# deska.net
KiCad netlist of a schematic drawn in EAGLE
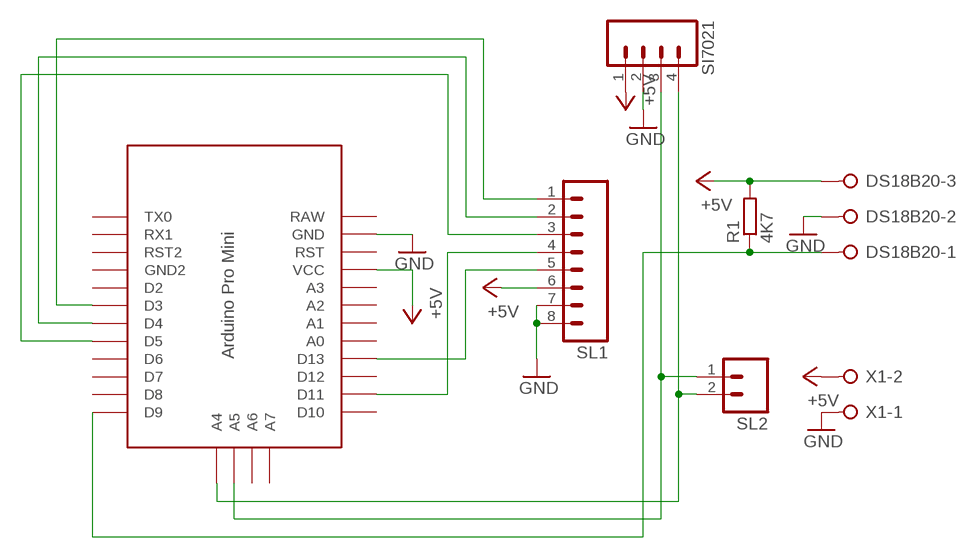
[diagram p0: schematic, sheet 1]

(export (version "E")
  (design (tool "Eeschema 10.0.6"))
  (components
    (comp (ref "DS18B20")
      (value "W237-03P")
      (footprint "eagle-import:W237-133")
      (libsource (lib "eagle-import") (part "W237-03P"))
    )
    (comp (ref "R1")
      (value "4K7")
      (footprint "eagle-import:0207_10")
      (libsource (lib "eagle-import") (part "R-EU_0207/10"))
    )
    (comp (ref "SI7021")
      (value "M04")
      (footprint "eagle-import:04P")
      (libsource (lib "eagle-import") (part "M04"))
    )
    (comp (ref "SL1")
      (value "M08")
      (footprint "eagle-import:08P")
      (libsource (lib "eagle-import") (part "M08"))
    )
    (comp (ref "SL2")
      (value "M02")
      (footprint "eagle-import:02P")
      (libsource (lib "eagle-import") (part "M02"))
    )
    (comp (ref "U$1")
      (value "PRO-MINI")
      (footprint "eagle-import:PRO-MINI")
      (libsource (lib "eagle-import") (part "PRO-MINI"))
    )
    (comp (ref "X1")
      (value "W237-02P")
      (footprint "eagle-import:W237-132")
      (libsource (lib "eagle-import") (part "W237-02P"))
    )
  )
  (nets
    (net (code "1") (name "+5V") (class "Default")
      (node (ref "DS18B20") (pin "3") (pinfunction "KL_3") (pintype "passive"))
      (node (ref "R1") (pin "2") (pinfunction "2_2") (pintype "passive"))
      (node (ref "SI7021") (pin "1") (pinfunction "1_1") (pintype "passive"))
      (node (ref "SL1") (pin "6") (pinfunction "6_6") (pintype "passive"))
      (node (ref "U$1") (pin "VCC") (pinfunction "VCC_VCC") (pintype "bidirectional"))
      (node (ref "X1") (pin "2") (pinfunction "KL_2") (pintype "passive"))
    )
    (net (code "2") (name "/RAW") (class "Default")
      (node (ref "U$1") (pin "RAW") (pinfunction "RAW_RAW") (pintype "power_in"))
    )
    (net (code "3") (name "GND") (class "Default")
      (node (ref "DS18B20") (pin "2") (pinfunction "KL_2") (pintype "passive"))
      (node (ref "SI7021") (pin "2") (pinfunction "2_2") (pintype "passive"))
      (node (ref "SL1") (pin "7") (pinfunction "7_7") (pintype "passive"))
      (node (ref "SL1") (pin "8") (pinfunction "8_8") (pintype "passive"))
      (node (ref "U$1") (pin "GND") (pinfunction "GND_GND") (pintype "input"))
      (node (ref "X1") (pin "1") (pinfunction "KL_1") (pintype "passive"))
    )
    (net (code "4") (name "Net-(DS18B20A-KL)") (class "Default")
      (node (ref "DS18B20") (pin "1") (pinfunction "KL_1") (pintype "passive"))
      (node (ref "R1") (pin "1") (pinfunction "1_1") (pintype "passive"))
      (node (ref "U$1") (pin "D9") (pinfunction "D9_D9") (pintype "bidirectional"))
    )
    (net (code "5") (name "Net-(SI7021-Pad3)") (class "Default")
      (node (ref "SI7021") (pin "3") (pinfunction "3_3") (pintype "passive"))
      (node (ref "SL2") (pin "1") (pinfunction "1_1") (pintype "passive"))
      (node (ref "U$1") (pin "A5") (pinfunction "A5_A5") (pintype "bidirectional"))
    )
    (net (code "6") (name "Net-(SI7021-Pad4)") (class "Default")
      (node (ref "SI7021") (pin "4") (pinfunction "4_4") (pintype "passive"))
      (node (ref "SL2") (pin "2") (pinfunction "2_2") (pintype "passive"))
      (node (ref "U$1") (pin "A4") (pinfunction "A4_A4") (pintype "bidirectional"))
    )
    (net (code "7") (name "Net-(SL1-Pad1)") (class "Default")
      (node (ref "SL1") (pin "1") (pinfunction "1_1") (pintype "passive"))
      (node (ref "U$1") (pin "D3") (pinfunction "D3_D3") (pintype "bidirectional"))
    )
    (net (code "8") (name "Net-(SL1-Pad2)") (class "Default")
      (node (ref "SL1") (pin "2") (pinfunction "2_2") (pintype "passive"))
      (node (ref "U$1") (pin "D4") (pinfunction "D4_D4") (pintype "bidirectional"))
    )
    (net (code "9") (name "Net-(SL1-Pad3)") (class "Default")
      (node (ref "SL1") (pin "3") (pinfunction "3_3") (pintype "passive"))
      (node (ref "U$1") (pin "D5") (pinfunction "D5_D5") (pintype "bidirectional"))
    )
    (net (code "10") (name "Net-(SL1-Pad4)") (class "Default")
      (node (ref "SL1") (pin "4") (pinfunction "4_4") (pintype "passive"))
      (node (ref "U$1") (pin "D11") (pinfunction "D11_D11") (pintype "bidirectional"))
    )
    (net (code "11") (name "Net-(SL1-Pad5)") (class "Default")
      (node (ref "SL1") (pin "5") (pinfunction "5_5") (pintype "passive"))
      (node (ref "U$1") (pin "D13") (pinfunction "D13_D13") (pintype "bidirectional"))
    )
    (net (code "12") (name "unconnected-(U$1-GND2-PadGND1)") (class "Default")
      (node (ref "U$1") (pin "GND1") (pinfunction "GND2_GND1") (pintype "bidirectional"))
    )
    (net (code "13") (name "unconnected-(U$1-PadA0)") (class "Default")
      (node (ref "U$1") (pin "A0") (pinfunction "A0_A0") (pintype "bidirectional"))
    )
    (net (code "14") (name "unconnected-(U$1-PadA1)") (class "Default")
      (node (ref "U$1") (pin "A1") (pinfunction "A1_A1") (pintype "bidirectional"))
    )
    (net (code "15") (name "unconnected-(U$1-PadA2)") (class "Default")
      (node (ref "U$1") (pin "A2") (pinfunction "A2_A2") (pintype "bidirectional"))
    )
    (net (code "16") (name "unconnected-(U$1-PadA3)") (class "Default")
      (node (ref "U$1") (pin "A3") (pinfunction "A3_A3") (pintype "bidirectional"))
    )
    (net (code "17") (name "unconnected-(U$1-PadA6)") (class "Default")
      (node (ref "U$1") (pin "A6") (pinfunction "A6_A6") (pintype "bidirectional"))
    )
    (net (code "18") (name "unconnected-(U$1-PadA7)") (class "Default")
      (node (ref "U$1") (pin "A7") (pinfunction "A7_A7") (pintype "bidirectional"))
    )
    (net (code "19") (name "unconnected-(U$1-PadD2)") (class "Default")
      (node (ref "U$1") (pin "D2") (pinfunction "D2_D2") (pintype "bidirectional"))
    )
    (net (code "20") (name "unconnected-(U$1-PadD6)") (class "Default")
      (node (ref "U$1") (pin "D6") (pinfunction "D6_D6") (pintype "bidirectional"))
    )
    (net (code "21") (name "unconnected-(U$1-PadD7)") (class "Default")
      (node (ref "U$1") (pin "D7") (pinfunction "D7_D7") (pintype "bidirectional"))
    )
    (net (code "22") (name "unconnected-(U$1-PadD8)") (class "Default")
      (node (ref "U$1") (pin "D8") (pinfunction "D8_D8") (pintype "bidirectional"))
    )
    (net (code "23") (name "unconnected-(U$1-PadD10)") (class "Default")
      (node (ref "U$1") (pin "D10") (pinfunction "D10_D10") (pintype "bidirectional"))
    )
    (net (code "24") (name "unconnected-(U$1-PadD12)") (class "Default")
      (node (ref "U$1") (pin "D12") (pinfunction "D12_D12") (pintype "bidirectional"))
    )
    (net (code "25") (name "unconnected-(U$1-PadRST)") (class "Default")
      (node (ref "U$1") (pin "RST") (pinfunction "RST_RST") (pintype "bidirectional"))
    )
    (net (code "26") (name "unconnected-(U$1-PadRX1)") (class "Default")
      (node (ref "U$1") (pin "RX1") (pinfunction "RX1_RX1") (pintype "bidirectional"))
    )
    (net (code "27") (name "unconnected-(U$1-PadTX0)") (class "Default")
      (node (ref "U$1") (pin "TX0") (pinfunction "TX0_TX0") (pintype "bidirectional"))
    )
    (net (code "28") (name "unconnected-(U$1-RST2-PadRST1)") (class "Default")
      (node (ref "U$1") (pin "RST1") (pinfunction "RST2_RST1") (pintype "bidirectional"))
    )
  )
)
